# 3_buttons_a.net
KiCad netlist of a schematic drawn in EAGLE
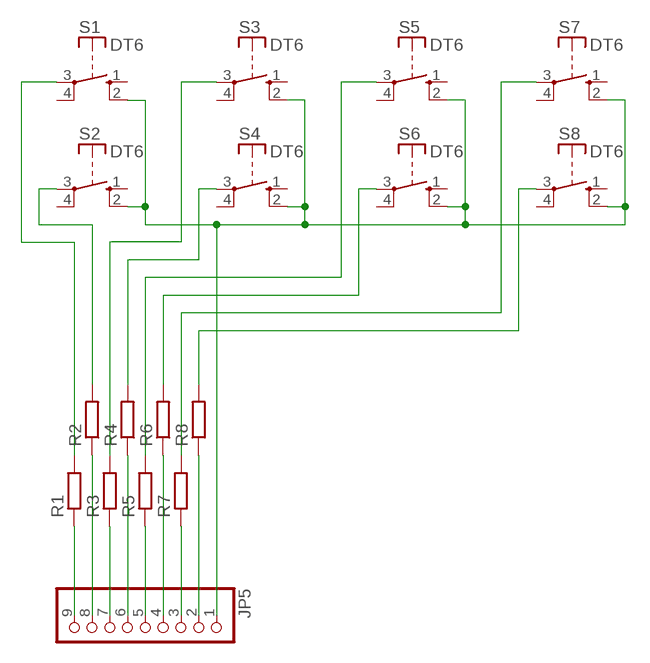
[diagram p0: schematic, sheet 1]

(export (version "E")
  (design (tool "Eeschema 10.0.6"))
  (components
    (comp (ref "JP5")
      (value "PINHD-1X09_2.54-90°")
      (footprint "eagle-import:1X09_90")
      (libsource (lib "eagle-import") (part "PINHD-1X09_2.54-90°"))
    )
    (comp (ref "R1")
      (value "R_0207")
      (footprint "eagle-import:R_0207_BIGPADS")
      (libsource (lib "eagle-import") (part "R_0207"))
    )
    (comp (ref "R2")
      (value "R_0207")
      (footprint "eagle-import:R_0207_BIGPADS")
      (libsource (lib "eagle-import") (part "R_0207"))
    )
    (comp (ref "R3")
      (value "R_0207")
      (footprint "eagle-import:R_0207_BIGPADS")
      (libsource (lib "eagle-import") (part "R_0207"))
    )
    (comp (ref "R4")
      (value "R_0207")
      (footprint "eagle-import:R_0207_BIGPADS")
      (libsource (lib "eagle-import") (part "R_0207"))
    )
    (comp (ref "R5")
      (value "R_0207")
      (footprint "eagle-import:R_0207_BIGPADS")
      (libsource (lib "eagle-import") (part "R_0207"))
    )
    (comp (ref "R6")
      (value "R_0207")
      (footprint "eagle-import:R_0207_BIGPADS")
      (libsource (lib "eagle-import") (part "R_0207"))
    )
    (comp (ref "R7")
      (value "R_0207")
      (footprint "eagle-import:R_0207_BIGPADS")
      (libsource (lib "eagle-import") (part "R_0207"))
    )
    (comp (ref "R8")
      (value "R_0207")
      (footprint "eagle-import:R_0207_BIGPADS")
      (libsource (lib "eagle-import") (part "R_0207"))
    )
    (comp (ref "S1")
      (value "DT6")
      (footprint "eagle-import:DT6")
      (libsource (lib "eagle-import") (part "DT6"))
    )
    (comp (ref "S2")
      (value "DT6")
      (footprint "eagle-import:DT6")
      (libsource (lib "eagle-import") (part "DT6"))
    )
    (comp (ref "S3")
      (value "DT6")
      (footprint "eagle-import:DT6")
      (libsource (lib "eagle-import") (part "DT6"))
    )
    (comp (ref "S4")
      (value "DT6")
      (footprint "eagle-import:DT6")
      (libsource (lib "eagle-import") (part "DT6"))
    )
    (comp (ref "S5")
      (value "DT6")
      (footprint "eagle-import:DT6")
      (libsource (lib "eagle-import") (part "DT6"))
    )
    (comp (ref "S6")
      (value "DT6")
      (footprint "eagle-import:DT6")
      (libsource (lib "eagle-import") (part "DT6"))
    )
    (comp (ref "S7")
      (value "DT6")
      (footprint "eagle-import:DT6")
      (libsource (lib "eagle-import") (part "DT6"))
    )
    (comp (ref "S8")
      (value "DT6")
      (footprint "eagle-import:DT6")
      (libsource (lib "eagle-import") (part "DT6"))
    )
  )
  (nets
    (net (code "1") (name "Net-(JP5-Pad1)") (class "Default")
      (node (ref "JP5") (pin "1") (pinfunction "1_1") (pintype "passive"))
      (node (ref "S1") (pin "2") (pinfunction "S_2") (pintype "passive"))
      (node (ref "S2") (pin "2") (pinfunction "S_2") (pintype "passive"))
      (node (ref "S3") (pin "2") (pinfunction "S_2") (pintype "passive"))
      (node (ref "S4") (pin "2") (pinfunction "S_2") (pintype "passive"))
      (node (ref "S5") (pin "2") (pinfunction "S_2") (pintype "passive"))
      (node (ref "S6") (pin "2") (pinfunction "S_2") (pintype "passive"))
      (node (ref "S7") (pin "2") (pinfunction "S_2") (pintype "passive"))
      (node (ref "S8") (pin "2") (pinfunction "S_2") (pintype "passive"))
    )
    (net (code "2") (name "Net-(R1-1)") (class "Default")
      (node (ref "JP5") (pin "9") (pinfunction "9_9") (pintype "passive"))
      (node (ref "R1") (pin "P$1") (pinfunction "1_P$1") (pintype "passive"))
    )
    (net (code "3") (name "Net-(R1-2)") (class "Default")
      (node (ref "R1") (pin "P$2") (pinfunction "2_P$2") (pintype "passive"))
      (node (ref "S1") (pin "3") (pinfunction "P_3") (pintype "passive"))
    )
    (net (code "4") (name "Net-(R2-1)") (class "Default")
      (node (ref "JP5") (pin "8") (pinfunction "8_8") (pintype "passive"))
      (node (ref "R2") (pin "P$1") (pinfunction "1_P$1") (pintype "passive"))
    )
    (net (code "5") (name "Net-(R2-2)") (class "Default")
      (node (ref "R2") (pin "P$2") (pinfunction "2_P$2") (pintype "passive"))
      (node (ref "S2") (pin "3") (pinfunction "P_3") (pintype "passive"))
    )
    (net (code "6") (name "Net-(R3-1)") (class "Default")
      (node (ref "JP5") (pin "7") (pinfunction "7_7") (pintype "passive"))
      (node (ref "R3") (pin "P$1") (pinfunction "1_P$1") (pintype "passive"))
    )
    (net (code "7") (name "Net-(R3-2)") (class "Default")
      (node (ref "R3") (pin "P$2") (pinfunction "2_P$2") (pintype "passive"))
      (node (ref "S3") (pin "3") (pinfunction "P_3") (pintype "passive"))
    )
    (net (code "8") (name "Net-(R4-1)") (class "Default")
      (node (ref "JP5") (pin "6") (pinfunction "6_6") (pintype "passive"))
      (node (ref "R4") (pin "P$1") (pinfunction "1_P$1") (pintype "passive"))
    )
    (net (code "9") (name "Net-(R4-2)") (class "Default")
      (node (ref "R4") (pin "P$2") (pinfunction "2_P$2") (pintype "passive"))
      (node (ref "S4") (pin "3") (pinfunction "P_3") (pintype "passive"))
    )
    (net (code "10") (name "Net-(R5-1)") (class "Default")
      (node (ref "JP5") (pin "5") (pinfunction "5_5") (pintype "passive"))
      (node (ref "R5") (pin "P$1") (pinfunction "1_P$1") (pintype "passive"))
    )
    (net (code "11") (name "Net-(R5-2)") (class "Default")
      (node (ref "R5") (pin "P$2") (pinfunction "2_P$2") (pintype "passive"))
      (node (ref "S5") (pin "3") (pinfunction "P_3") (pintype "passive"))
    )
    (net (code "12") (name "Net-(R6-1)") (class "Default")
      (node (ref "JP5") (pin "4") (pinfunction "4_4") (pintype "passive"))
      (node (ref "R6") (pin "P$1") (pinfunction "1_P$1") (pintype "passive"))
    )
    (net (code "13") (name "Net-(R6-2)") (class "Default")
      (node (ref "R6") (pin "P$2") (pinfunction "2_P$2") (pintype "passive"))
      (node (ref "S6") (pin "3") (pinfunction "P_3") (pintype "passive"))
    )
    (net (code "14") (name "Net-(R7-1)") (class "Default")
      (node (ref "JP5") (pin "3") (pinfunction "3_3") (pintype "passive"))
      (node (ref "R7") (pin "P$1") (pinfunction "1_P$1") (pintype "passive"))
    )
    (net (code "15") (name "Net-(R7-2)") (class "Default")
      (node (ref "R7") (pin "P$2") (pinfunction "2_P$2") (pintype "passive"))
      (node (ref "S7") (pin "3") (pinfunction "P_3") (pintype "passive"))
    )
    (net (code "16") (name "Net-(R8-1)") (class "Default")
      (node (ref "JP5") (pin "2") (pinfunction "2_2") (pintype "passive"))
      (node (ref "R8") (pin "P$1") (pinfunction "1_P$1") (pintype "passive"))
    )
    (net (code "17") (name "Net-(R8-2)") (class "Default")
      (node (ref "R8") (pin "P$2") (pinfunction "2_P$2") (pintype "passive"))
      (node (ref "S8") (pin "3") (pinfunction "P_3") (pintype "passive"))
    )
    (net (code "18") (name "unconnected-(S1-P-Pad4)") (class "Default")
      (node (ref "S1") (pin "4") (pinfunction "P_4") (pintype "passive"))
    )
    (net (code "19") (name "unconnected-(S1-S-Pad1)") (class "Default")
      (node (ref "S1") (pin "1") (pinfunction "S_1") (pintype "passive"))
    )
    (net (code "20") (name "unconnected-(S2-P-Pad4)") (class "Default")
      (node (ref "S2") (pin "4") (pinfunction "P_4") (pintype "passive"))
    )
    (net (code "21") (name "unconnected-(S2-S-Pad1)") (class "Default")
      (node (ref "S2") (pin "1") (pinfunction "S_1") (pintype "passive"))
    )
    (net (code "22") (name "unconnected-(S3-P-Pad4)") (class "Default")
      (node (ref "S3") (pin "4") (pinfunction "P_4") (pintype "passive"))
    )
    (net (code "23") (name "unconnected-(S3-S-Pad1)") (class "Default")
      (node (ref "S3") (pin "1") (pinfunction "S_1") (pintype "passive"))
    )
    (net (code "24") (name "unconnected-(S4-P-Pad4)") (class "Default")
      (node (ref "S4") (pin "4") (pinfunction "P_4") (pintype "passive"))
    )
    (net (code "25") (name "unconnected-(S4-S-Pad1)") (class "Default")
      (node (ref "S4") (pin "1") (pinfunction "S_1") (pintype "passive"))
    )
    (net (code "26") (name "unconnected-(S5-P-Pad4)") (class "Default")
      (node (ref "S5") (pin "4") (pinfunction "P_4") (pintype "passive"))
    )
    (net (code "27") (name "unconnected-(S5-S-Pad1)") (class "Default")
      (node (ref "S5") (pin "1") (pinfunction "S_1") (pintype "passive"))
    )
    (net (code "28") (name "unconnected-(S6-P-Pad4)") (class "Default")
      (node (ref "S6") (pin "4") (pinfunction "P_4") (pintype "passive"))
    )
    (net (code "29") (name "unconnected-(S6-S-Pad1)") (class "Default")
      (node (ref "S6") (pin "1") (pinfunction "S_1") (pintype "passive"))
    )
    (net (code "30") (name "unconnected-(S7-P-Pad4)") (class "Default")
      (node (ref "S7") (pin "4") (pinfunction "P_4") (pintype "passive"))
    )
    (net (code "31") (name "unconnected-(S7-S-Pad1)") (class "Default")
      (node (ref "S7") (pin "1") (pinfunction "S_1") (pintype "passive"))
    )
    (net (code "32") (name "unconnected-(S8-P-Pad4)") (class "Default")
      (node (ref "S8") (pin "4") (pinfunction "P_4") (pintype "passive"))
    )
    (net (code "33") (name "unconnected-(S8-S-Pad1)") (class "Default")
      (node (ref "S8") (pin "1") (pinfunction "S_1") (pintype "passive"))
    )
  )
)
